# TRV_SX1231_V0_1.net
KiCad netlist of a schematic drawn in EAGLE
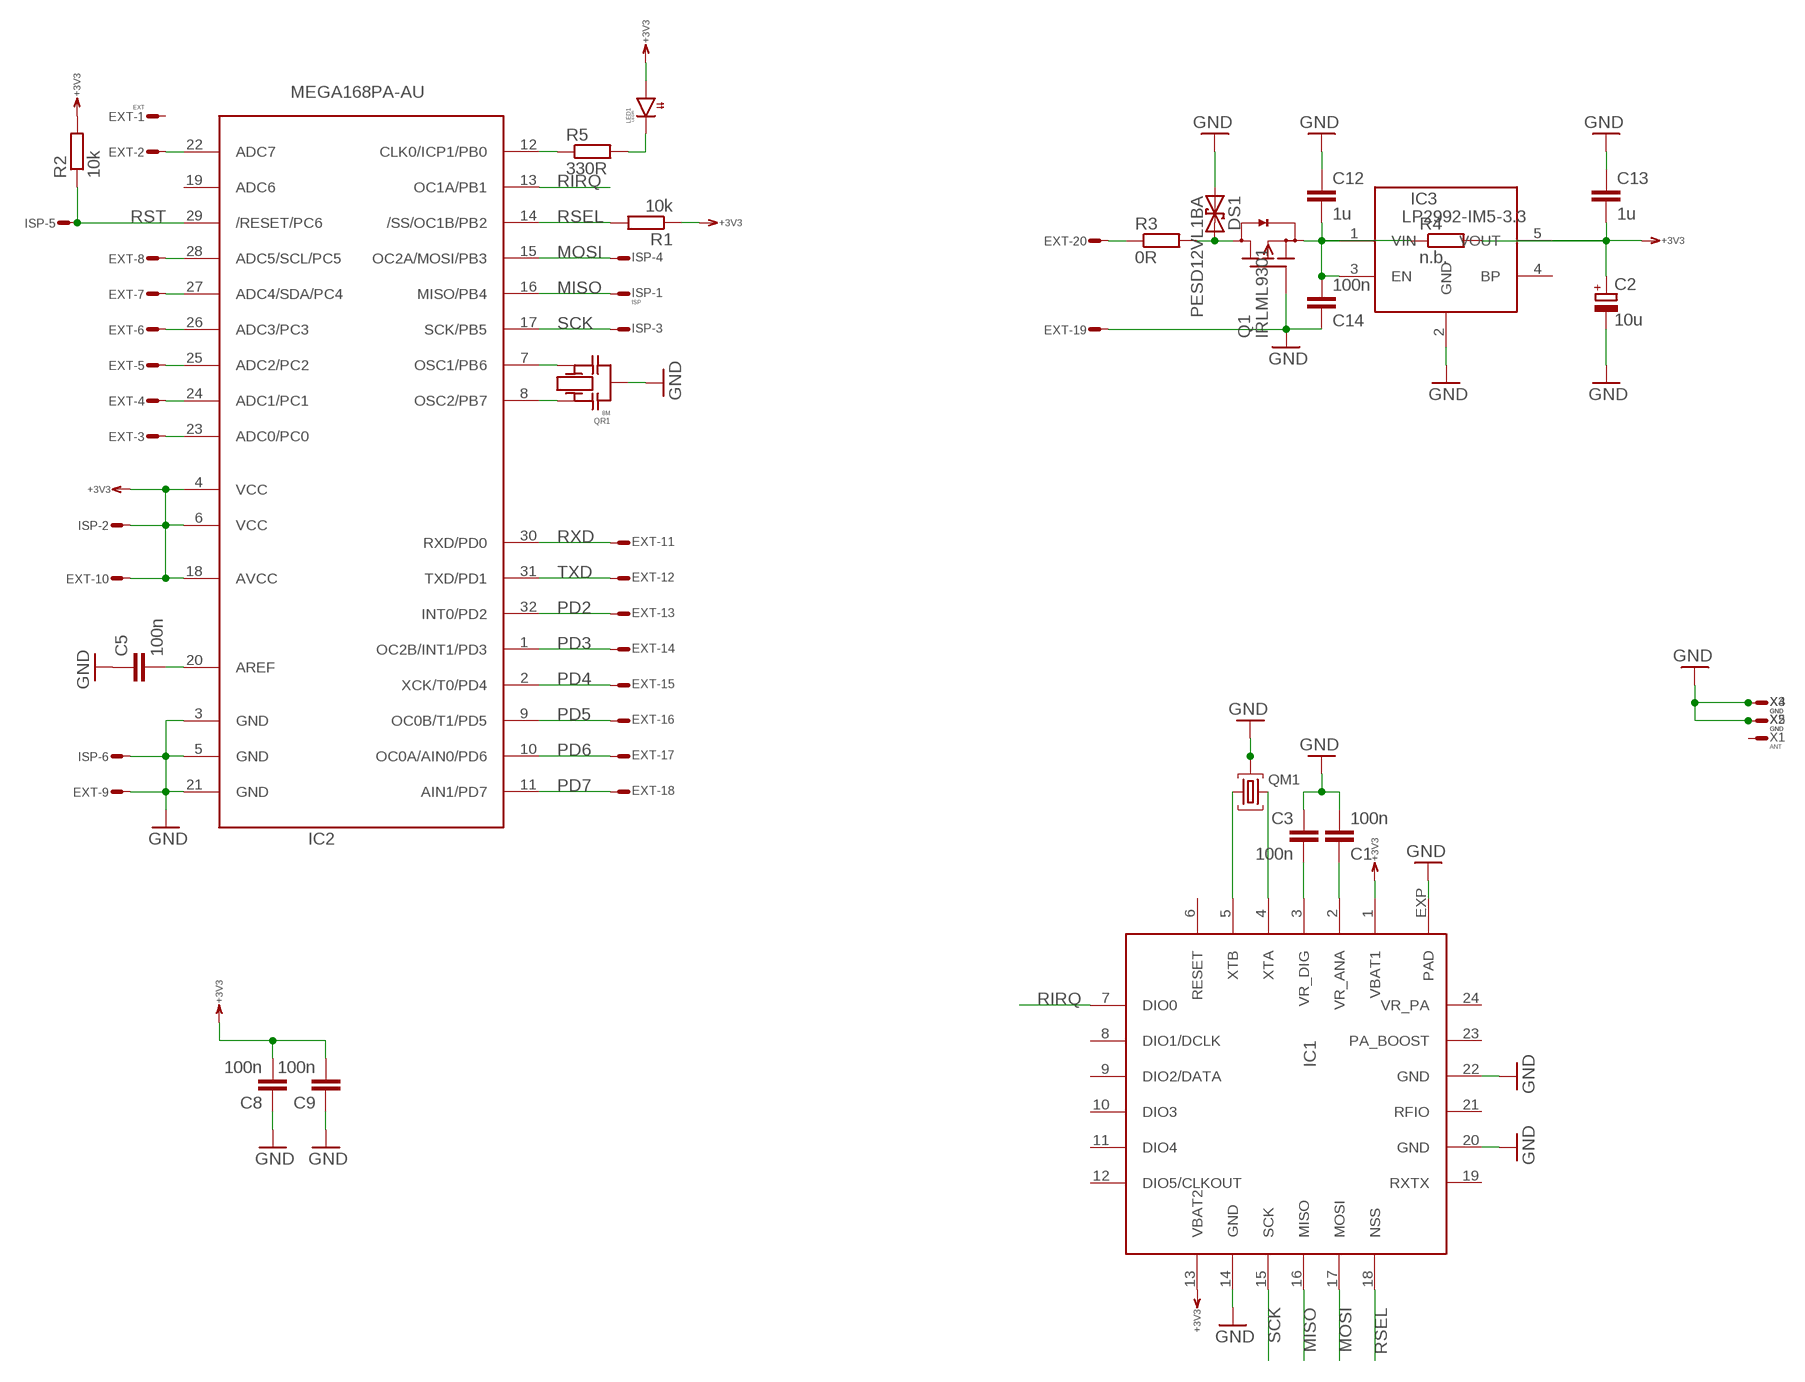
[diagram p0: schematic, sheet 1]

(export (version "E")
  (design (tool "Eeschema 10.0.6"))
  (components
    (comp (ref "C1")
      (value "100n")
      (footprint "eagle-import:0603")
      (libsource (lib "eagle-import") (part "C0603"))
    )
    (comp (ref "C2")
      (value "10u")
      (footprint "eagle-import:SMC_B")
      (libsource (lib "eagle-import") (part "C_POLSMCB"))
    )
    (comp (ref "C3")
      (value "100n")
      (footprint "eagle-import:0603")
      (libsource (lib "eagle-import") (part "C0603"))
    )
    (comp (ref "C5")
      (value "100n")
      (footprint "eagle-import:0603")
      (libsource (lib "eagle-import") (part "C0603"))
    )
    (comp (ref "C8")
      (value "100n")
      (footprint "eagle-import:0603")
      (libsource (lib "eagle-import") (part "C0603"))
    )
    (comp (ref "C9")
      (value "100n")
      (footprint "eagle-import:0603")
      (libsource (lib "eagle-import") (part "C0603"))
    )
    (comp (ref "C12")
      (value "1u")
      (footprint "eagle-import:0603")
      (libsource (lib "eagle-import") (part "C0603"))
    )
    (comp (ref "C13")
      (value "1u")
      (footprint "eagle-import:0603")
      (libsource (lib "eagle-import") (part "C0603"))
    )
    (comp (ref "C14")
      (value "100n")
      (footprint "eagle-import:0603")
      (libsource (lib "eagle-import") (part "C0603"))
    )
    (comp (ref "DS1")
      (value "PESD12VL1BA")
      (footprint "eagle-import:SOD323")
      (libsource (lib "eagle-import") (part "TVS-U323"))
    )
    (comp (ref "EXT")
      (value "EXT")
      (footprint "eagle-import:ML20S")
      (libsource (lib "eagle-import") (part "ML20?ES"))
    )
    (comp (ref "IC1")
      (value "SX1231")
      (footprint "eagle-import:QFN24")
      (libsource (lib "eagle-import") (part "SX1231"))
    )
    (comp (ref "IC2")
      (value "MEGA168PA-AU")
      (footprint "eagle-import:TQFP32-08")
      (libsource (lib "eagle-import") (part "MEGA168PA"))
    )
    (comp (ref "IC3")
      (value "LP2992-IM5-3.3")
      (footprint "eagle-import:SOT23-5")
      (libsource (lib "eagle-import") (part "LDO"))
    )
    (comp (ref "ISP")
      (value "ISP")
      (footprint "eagle-import:ML6S")
      (libsource (lib "eagle-import") (part "ML6ES"))
    )
    (comp (ref "LED1")
      (value "LEDR")
      (footprint "eagle-import:0603")
      (libsource (lib "eagle-import") (part "LED0603"))
    )
    (comp (ref "Q1")
      (value "IRLML9301")
      (footprint "eagle-import:SOT23")
      (libsource (lib "eagle-import") (part "FET-PDSOT23"))
    )
    (comp (ref "QM1")
      (value "QM5X3.2")
      (footprint "eagle-import:ABM3C")
      (libsource (lib "eagle-import") (part "QM5X3.2"))
    )
    (comp (ref "QR1")
      (value "8M")
      (footprint "eagle-import:CR")
      (libsource (lib "eagle-import") (part "QRCR"))
    )
    (comp (ref "R1")
      (value "10k")
      (footprint "eagle-import:0603")
      (libsource (lib "eagle-import") (part "R0603"))
    )
    (comp (ref "R2")
      (value "10k")
      (footprint "eagle-import:0603")
      (libsource (lib "eagle-import") (part "R0603"))
    )
    (comp (ref "R3")
      (value "0R")
      (footprint "eagle-import:0603")
      (libsource (lib "eagle-import") (part "R0603"))
    )
    (comp (ref "R4")
      (value "n.b.")
      (footprint "eagle-import:0603")
      (libsource (lib "eagle-import") (part "R0603"))
    )
    (comp (ref "R5")
      (value "330R")
      (footprint "eagle-import:0603")
      (libsource (lib "eagle-import") (part "R0603"))
    )
    (comp (ref "X1")
      (value "ANT")
      (footprint "eagle-import:S2.54_1.27")
      (libsource (lib "eagle-import") (part "WIREPADS2.54/1.27"))
    )
    (comp (ref "X2")
      (value "GND")
      (footprint "eagle-import:S2.54_1.27")
      (libsource (lib "eagle-import") (part "WIREPADS2.54/1.27"))
    )
    (comp (ref "X3")
      (value "GND")
      (footprint "eagle-import:S2.54_1.27")
      (libsource (lib "eagle-import") (part "WIREPADS2.54/1.27"))
    )
    (comp (ref "X4")
      (value "GND")
      (footprint "eagle-import:S2.54_1.27")
      (libsource (lib "eagle-import") (part "WIREPADS2.54/1.27"))
    )
    (comp (ref "X5")
      (value "GND")
      (footprint "eagle-import:S2.54_1.27")
      (libsource (lib "eagle-import") (part "WIREPADS2.54/1.27"))
    )
  )
  (nets
    (net (code "1") (name "+3V3") (class "Default")
      (node (ref "C13") (pin "2") (pinfunction "2_2") (pintype "passive"))
      (node (ref "C2") (pin "+") (pinfunction "+_+") (pintype "passive"))
      (node (ref "C8") (pin "2") (pinfunction "2_2") (pintype "passive"))
      (node (ref "C9") (pin "2") (pinfunction "2_2") (pintype "passive"))
      (node (ref "EXT") (pin "10") (pinfunction "S_10") (pintype "passive"))
      (node (ref "IC1") (pin "1") (pinfunction "VBAT1_1") (pintype "bidirectional"))
      (node (ref "IC1") (pin "13") (pinfunction "VBAT2_13") (pintype "bidirectional"))
      (node (ref "IC2") (pin "18") (pinfunction "AVCC_18") (pintype "bidirectional"))
      (node (ref "IC2") (pin "4") (pinfunction "VCC_4") (pintype "bidirectional"))
      (node (ref "IC2") (pin "6") (pinfunction "VCC_6") (pintype "bidirectional"))
      (node (ref "IC3") (pin "5") (pinfunction "VOUT_5") (pintype "bidirectional"))
      (node (ref "ISP") (pin "2") (pinfunction "S_2") (pintype "passive"))
      (node (ref "LED1") (pin "1") (pinfunction "A_1") (pintype "bidirectional"))
      (node (ref "R1") (pin "1") (pinfunction "1_1") (pintype "passive"))
      (node (ref "R2") (pin "2") (pinfunction "2_2") (pintype "passive"))
      (node (ref "R4") (pin "2") (pinfunction "2_2") (pintype "passive"))
    )
    (net (code "2") (name "/MISO") (class "Default")
      (node (ref "IC1") (pin "16") (pinfunction "MISO_16") (pintype "output"))
      (node (ref "IC2") (pin "16") (pinfunction "MISO/PB4_16") (pintype "bidirectional"))
      (node (ref "ISP") (pin "1") (pinfunction "S_1") (pintype "passive"))
    )
    (net (code "3") (name "/MOSI") (class "Default")
      (node (ref "IC1") (pin "17") (pinfunction "MOSI_17") (pintype "input"))
      (node (ref "IC2") (pin "15") (pinfunction "OC2A/MOSI/PB3_15") (pintype "bidirectional"))
      (node (ref "ISP") (pin "4") (pinfunction "S_4") (pintype "passive"))
    )
    (net (code "4") (name "/PD2") (class "Default")
      (node (ref "EXT") (pin "13") (pinfunction "S_13") (pintype "passive"))
      (node (ref "IC2") (pin "32") (pinfunction "INT0/PD2_32") (pintype "bidirectional"))
    )
    (net (code "5") (name "/PD3") (class "Default")
      (node (ref "EXT") (pin "14") (pinfunction "S_14") (pintype "passive"))
      (node (ref "IC2") (pin "1") (pinfunction "OC2B/INT1/PD3_1") (pintype "bidirectional"))
    )
    (net (code "6") (name "/PD4") (class "Default")
      (node (ref "EXT") (pin "15") (pinfunction "S_15") (pintype "passive"))
      (node (ref "IC2") (pin "2") (pinfunction "XCK/T0/PD4_2") (pintype "bidirectional"))
    )
    (net (code "7") (name "/PD5") (class "Default")
      (node (ref "EXT") (pin "16") (pinfunction "S_16") (pintype "passive"))
      (node (ref "IC2") (pin "9") (pinfunction "OC0B/T1/PD5_9") (pintype "bidirectional"))
    )
    (net (code "8") (name "/PD6") (class "Default")
      (node (ref "EXT") (pin "17") (pinfunction "S_17") (pintype "passive"))
      (node (ref "IC2") (pin "10") (pinfunction "OC0A/AIN0/PD6_10") (pintype "bidirectional"))
    )
    (net (code "9") (name "/PD7") (class "Default")
      (node (ref "EXT") (pin "18") (pinfunction "S_18") (pintype "passive"))
      (node (ref "IC2") (pin "11") (pinfunction "AIN1/PD7_11") (pintype "bidirectional"))
    )
    (net (code "10") (name "/RIRQ") (class "Default")
      (node (ref "IC1") (pin "7") (pinfunction "DIO0_7") (pintype "bidirectional"))
      (node (ref "IC2") (pin "13") (pinfunction "OC1A/PB1_13") (pintype "bidirectional"))
    )
    (net (code "11") (name "/RSEL") (class "Default")
      (node (ref "IC1") (pin "18") (pinfunction "NSS_18") (pintype "input"))
      (node (ref "IC2") (pin "14") (pinfunction "/SS/OC1B/PB2_14") (pintype "bidirectional"))
      (node (ref "R1") (pin "2") (pinfunction "2_2") (pintype "passive"))
    )
    (net (code "12") (name "/RST") (class "Default")
      (node (ref "IC2") (pin "29") (pinfunction "/RESET/PC6_29") (pintype "bidirectional"))
      (node (ref "ISP") (pin "5") (pinfunction "S_5") (pintype "passive"))
      (node (ref "R2") (pin "1") (pinfunction "1_1") (pintype "passive"))
    )
    (net (code "13") (name "/RXD") (class "Default")
      (node (ref "EXT") (pin "11") (pinfunction "S_11") (pintype "passive"))
      (node (ref "IC2") (pin "30") (pinfunction "RXD/PD0_30") (pintype "bidirectional"))
    )
    (net (code "14") (name "/SCK") (class "Default")
      (node (ref "IC1") (pin "15") (pinfunction "SCK_15") (pintype "input"))
      (node (ref "IC2") (pin "17") (pinfunction "SCK/PB5_17") (pintype "bidirectional"))
      (node (ref "ISP") (pin "3") (pinfunction "S_3") (pintype "passive"))
    )
    (net (code "15") (name "/TXD") (class "Default")
      (node (ref "EXT") (pin "12") (pinfunction "S_12") (pintype "passive"))
      (node (ref "IC2") (pin "31") (pinfunction "TXD/PD1_31") (pintype "bidirectional"))
    )
    (net (code "16") (name "GND") (class "Default")
      (node (ref "C1") (pin "2") (pinfunction "2_2") (pintype "passive"))
      (node (ref "C12") (pin "1") (pinfunction "1_1") (pintype "passive"))
      (node (ref "C13") (pin "1") (pinfunction "1_1") (pintype "passive"))
      (node (ref "C14") (pin "1") (pinfunction "1_1") (pintype "passive"))
      (node (ref "C2") (pin "-") (pinfunction "-_-") (pintype "passive"))
      (node (ref "C3") (pin "1") (pinfunction "1_1") (pintype "passive"))
      (node (ref "C5") (pin "1") (pinfunction "1_1") (pintype "passive"))
      (node (ref "C8") (pin "1") (pinfunction "1_1") (pintype "passive"))
      (node (ref "C9") (pin "1") (pinfunction "1_1") (pintype "passive"))
      (node (ref "DS1") (pin "A") (pinfunction "1_A") (pintype "passive"))
      (node (ref "EXT") (pin "19") (pinfunction "S_19") (pintype "passive"))
      (node (ref "EXT") (pin "9") (pinfunction "S_9") (pintype "passive"))
      (node (ref "IC1") (pin "14") (pinfunction "GND_14") (pintype "bidirectional"))
      (node (ref "IC1") (pin "20") (pinfunction "GND_20") (pintype "bidirectional"))
      (node (ref "IC1") (pin "22") (pinfunction "GND_22") (pintype "bidirectional"))
      (node (ref "IC1") (pin "EXP") (pinfunction "PAD_EXP") (pintype "bidirectional"))
      (node (ref "IC2") (pin "21") (pinfunction "GND_21") (pintype "bidirectional"))
      (node (ref "IC2") (pin "3") (pinfunction "GND_3") (pintype "bidirectional"))
      (node (ref "IC2") (pin "5") (pinfunction "GND_5") (pintype "bidirectional"))
      (node (ref "IC3") (pin "2") (pinfunction "GND_2") (pintype "bidirectional"))
      (node (ref "ISP") (pin "6") (pinfunction "S_6") (pintype "passive"))
      (node (ref "Q1") (pin "1") (pinfunction "G_1") (pintype "passive"))
      (node (ref "QM1") (pin "P$2") (pinfunction "M1_P$2") (pintype "passive"))
      (node (ref "QM1") (pin "P$4") (pinfunction "M2_P$4") (pintype "passive"))
      (node (ref "QR1") (pin "M") (pinfunction "M_M") (pintype "passive"))
      (node (ref "X2") (pin "1") (pinfunction "S_1") (pintype "passive"))
      (node (ref "X3") (pin "1") (pinfunction "S_1") (pintype "passive"))
      (node (ref "X4") (pin "1") (pinfunction "S_1") (pintype "passive"))
      (node (ref "X5") (pin "1") (pinfunction "S_1") (pintype "passive"))
    )
    (net (code "17") (name "Net-(DS1-2)") (class "Default")
      (node (ref "DS1") (pin "C") (pinfunction "2_C") (pintype "passive"))
      (node (ref "Q1") (pin "3") (pinfunction "D_3") (pintype "passive"))
      (node (ref "R3") (pin "2") (pinfunction "2_2") (pintype "passive"))
    )
    (net (code "18") (name "Net-(EXTL-S)") (class "Default")
      (node (ref "EXT") (pin "2") (pinfunction "S_2") (pintype "passive"))
      (node (ref "IC2") (pin "22") (pinfunction "ADC7_22") (pintype "bidirectional"))
    )
    (net (code "19") (name "Net-(EXTM-S)") (class "Default")
      (node (ref "EXT") (pin "20") (pinfunction "S_20") (pintype "passive"))
      (node (ref "R3") (pin "1") (pinfunction "1_1") (pintype "passive"))
    )
    (net (code "20") (name "Net-(EXTN-S)") (class "Default")
      (node (ref "EXT") (pin "3") (pinfunction "S_3") (pintype "passive"))
      (node (ref "IC2") (pin "23") (pinfunction "ADC0/PC0_23") (pintype "bidirectional"))
    )
    (net (code "21") (name "Net-(EXTO-S)") (class "Default")
      (node (ref "EXT") (pin "4") (pinfunction "S_4") (pintype "passive"))
      (node (ref "IC2") (pin "24") (pinfunction "ADC1/PC1_24") (pintype "bidirectional"))
    )
    (net (code "22") (name "Net-(EXTP-S)") (class "Default")
      (node (ref "EXT") (pin "5") (pinfunction "S_5") (pintype "passive"))
      (node (ref "IC2") (pin "25") (pinfunction "ADC2/PC2_25") (pintype "bidirectional"))
    )
    (net (code "23") (name "Net-(EXTQ-S)") (class "Default")
      (node (ref "EXT") (pin "6") (pinfunction "S_6") (pintype "passive"))
      (node (ref "IC2") (pin "26") (pinfunction "ADC3/PC3_26") (pintype "bidirectional"))
    )
    (net (code "24") (name "Net-(EXTR-S)") (class "Default")
      (node (ref "EXT") (pin "7") (pinfunction "S_7") (pintype "passive"))
      (node (ref "IC2") (pin "27") (pinfunction "ADC4/SDA/PC4_27") (pintype "bidirectional"))
    )
    (net (code "25") (name "Net-(EXTS-S)") (class "Default")
      (node (ref "EXT") (pin "8") (pinfunction "S_8") (pintype "passive"))
      (node (ref "IC2") (pin "28") (pinfunction "ADC5/SCL/PC5_28") (pintype "bidirectional"))
    )
    (net (code "26") (name "Net-(IC1-VR_ANA)") (class "Default")
      (node (ref "C1") (pin "1") (pinfunction "1_1") (pintype "passive"))
      (node (ref "IC1") (pin "2") (pinfunction "VR_ANA_2") (pintype "bidirectional"))
    )
    (net (code "27") (name "Net-(IC1-VR_DIG)") (class "Default")
      (node (ref "C3") (pin "2") (pinfunction "2_2") (pintype "passive"))
      (node (ref "IC1") (pin "3") (pinfunction "VR_DIG_3") (pintype "bidirectional"))
    )
    (net (code "28") (name "Net-(IC1-XTA)") (class "Default")
      (node (ref "IC1") (pin "4") (pinfunction "XTA_4") (pintype "bidirectional"))
      (node (ref "QM1") (pin "P$3") (pinfunction "2_P$3") (pintype "passive"))
    )
    (net (code "29") (name "Net-(IC1-XTB)") (class "Default")
      (node (ref "IC1") (pin "5") (pinfunction "XTB_5") (pintype "bidirectional"))
      (node (ref "QM1") (pin "P$1") (pinfunction "1_P$1") (pintype "passive"))
    )
    (net (code "30") (name "Net-(IC2-AREF)") (class "Default")
      (node (ref "C5") (pin "2") (pinfunction "2_2") (pintype "passive"))
      (node (ref "IC2") (pin "20") (pinfunction "AREF_20") (pintype "bidirectional"))
    )
    (net (code "31") (name "Net-(IC2-CLK0{slash}ICP1{slash}PB0)") (class "Default")
      (node (ref "IC2") (pin "12") (pinfunction "CLK0/ICP1/PB0_12") (pintype "bidirectional"))
      (node (ref "R5") (pin "1") (pinfunction "1_1") (pintype "passive"))
    )
    (net (code "32") (name "Net-(IC2-OSC1{slash}PB6)") (class "Default")
      (node (ref "IC2") (pin "7") (pinfunction "OSC1/PB6_7") (pintype "bidirectional"))
      (node (ref "QR1") (pin "2") (pinfunction "2_2") (pintype "passive"))
    )
    (net (code "33") (name "Net-(IC2-OSC2{slash}PB7)") (class "Default")
      (node (ref "IC2") (pin "8") (pinfunction "OSC2/PB7_8") (pintype "bidirectional"))
      (node (ref "QR1") (pin "1") (pinfunction "1_1") (pintype "passive"))
    )
    (net (code "34") (name "Net-(IC3-EN)") (class "Default")
      (node (ref "C12") (pin "2") (pinfunction "2_2") (pintype "passive"))
      (node (ref "C14") (pin "2") (pinfunction "2_2") (pintype "passive"))
      (node (ref "IC3") (pin "1") (pinfunction "VIN_1") (pintype "bidirectional"))
      (node (ref "IC3") (pin "3") (pinfunction "EN_3") (pintype "bidirectional"))
      (node (ref "Q1") (pin "2") (pinfunction "S_2") (pintype "passive"))
      (node (ref "R4") (pin "1") (pinfunction "1_1") (pintype "passive"))
    )
    (net (code "35") (name "Net-(LED1-C)") (class "Default")
      (node (ref "LED1") (pin "2") (pinfunction "C_2") (pintype "bidirectional"))
      (node (ref "R5") (pin "2") (pinfunction "2_2") (pintype "passive"))
    )
    (net (code "36") (name "unconnected-(EXTA-S-Pad1)") (class "Default")
      (node (ref "EXT") (pin "1") (pinfunction "S_1") (pintype "passive"))
    )
    (net (code "37") (name "unconnected-(IC1-DIO1{slash}DCLK-Pad8)") (class "Default")
      (node (ref "IC1") (pin "8") (pinfunction "DIO1/DCLK_8") (pintype "bidirectional"))
    )
    (net (code "38") (name "unconnected-(IC1-DIO2{slash}DATA-Pad9)") (class "Default")
      (node (ref "IC1") (pin "9") (pinfunction "DIO2/DATA_9") (pintype "bidirectional"))
    )
    (net (code "39") (name "unconnected-(IC1-DIO3-Pad10)") (class "Default")
      (node (ref "IC1") (pin "10") (pinfunction "DIO3_10") (pintype "bidirectional"))
    )
    (net (code "40") (name "unconnected-(IC1-DIO4-Pad11)") (class "Default")
      (node (ref "IC1") (pin "11") (pinfunction "DIO4_11") (pintype "bidirectional"))
    )
    (net (code "41") (name "unconnected-(IC1-DIO5{slash}CLKOUT-Pad12)") (class "Default")
      (node (ref "IC1") (pin "12") (pinfunction "DIO5/CLKOUT_12") (pintype "bidirectional"))
    )
    (net (code "42") (name "unconnected-(IC1-PA_BOOST-Pad23)") (class "Default")
      (node (ref "IC1") (pin "23") (pinfunction "PA_BOOST_23") (pintype "output"))
    )
    (net (code "43") (name "unconnected-(IC1-RESET-Pad6)") (class "Default")
      (node (ref "IC1") (pin "6") (pinfunction "RESET_6") (pintype "bidirectional"))
    )
    (net (code "44") (name "unconnected-(IC1-RFIO-Pad21)") (class "Default")
      (node (ref "IC1") (pin "21") (pinfunction "RFIO_21") (pintype "bidirectional"))
    )
    (net (code "45") (name "unconnected-(IC1-RXTX-Pad19)") (class "Default")
      (node (ref "IC1") (pin "19") (pinfunction "RXTX_19") (pintype "output"))
    )
    (net (code "46") (name "unconnected-(IC1-VR_PA-Pad24)") (class "Default")
      (node (ref "IC1") (pin "24") (pinfunction "VR_PA_24") (pintype "bidirectional"))
    )
    (net (code "47") (name "unconnected-(IC2-ADC6-Pad19)") (class "Default")
      (node (ref "IC2") (pin "19") (pinfunction "ADC6_19") (pintype "bidirectional"))
    )
    (net (code "48") (name "unconnected-(IC3-BP-Pad4)") (class "Default")
      (node (ref "IC3") (pin "4") (pinfunction "BP_4") (pintype "bidirectional"))
    )
    (net (code "49") (name "unconnected-(X1-S-Pad1)") (class "Default")
      (node (ref "X1") (pin "1") (pinfunction "S_1") (pintype "passive"))
    )
  )
)
